# AEMSUCA-R2.net
KiCad netlist of a schematic drawn in EAGLE
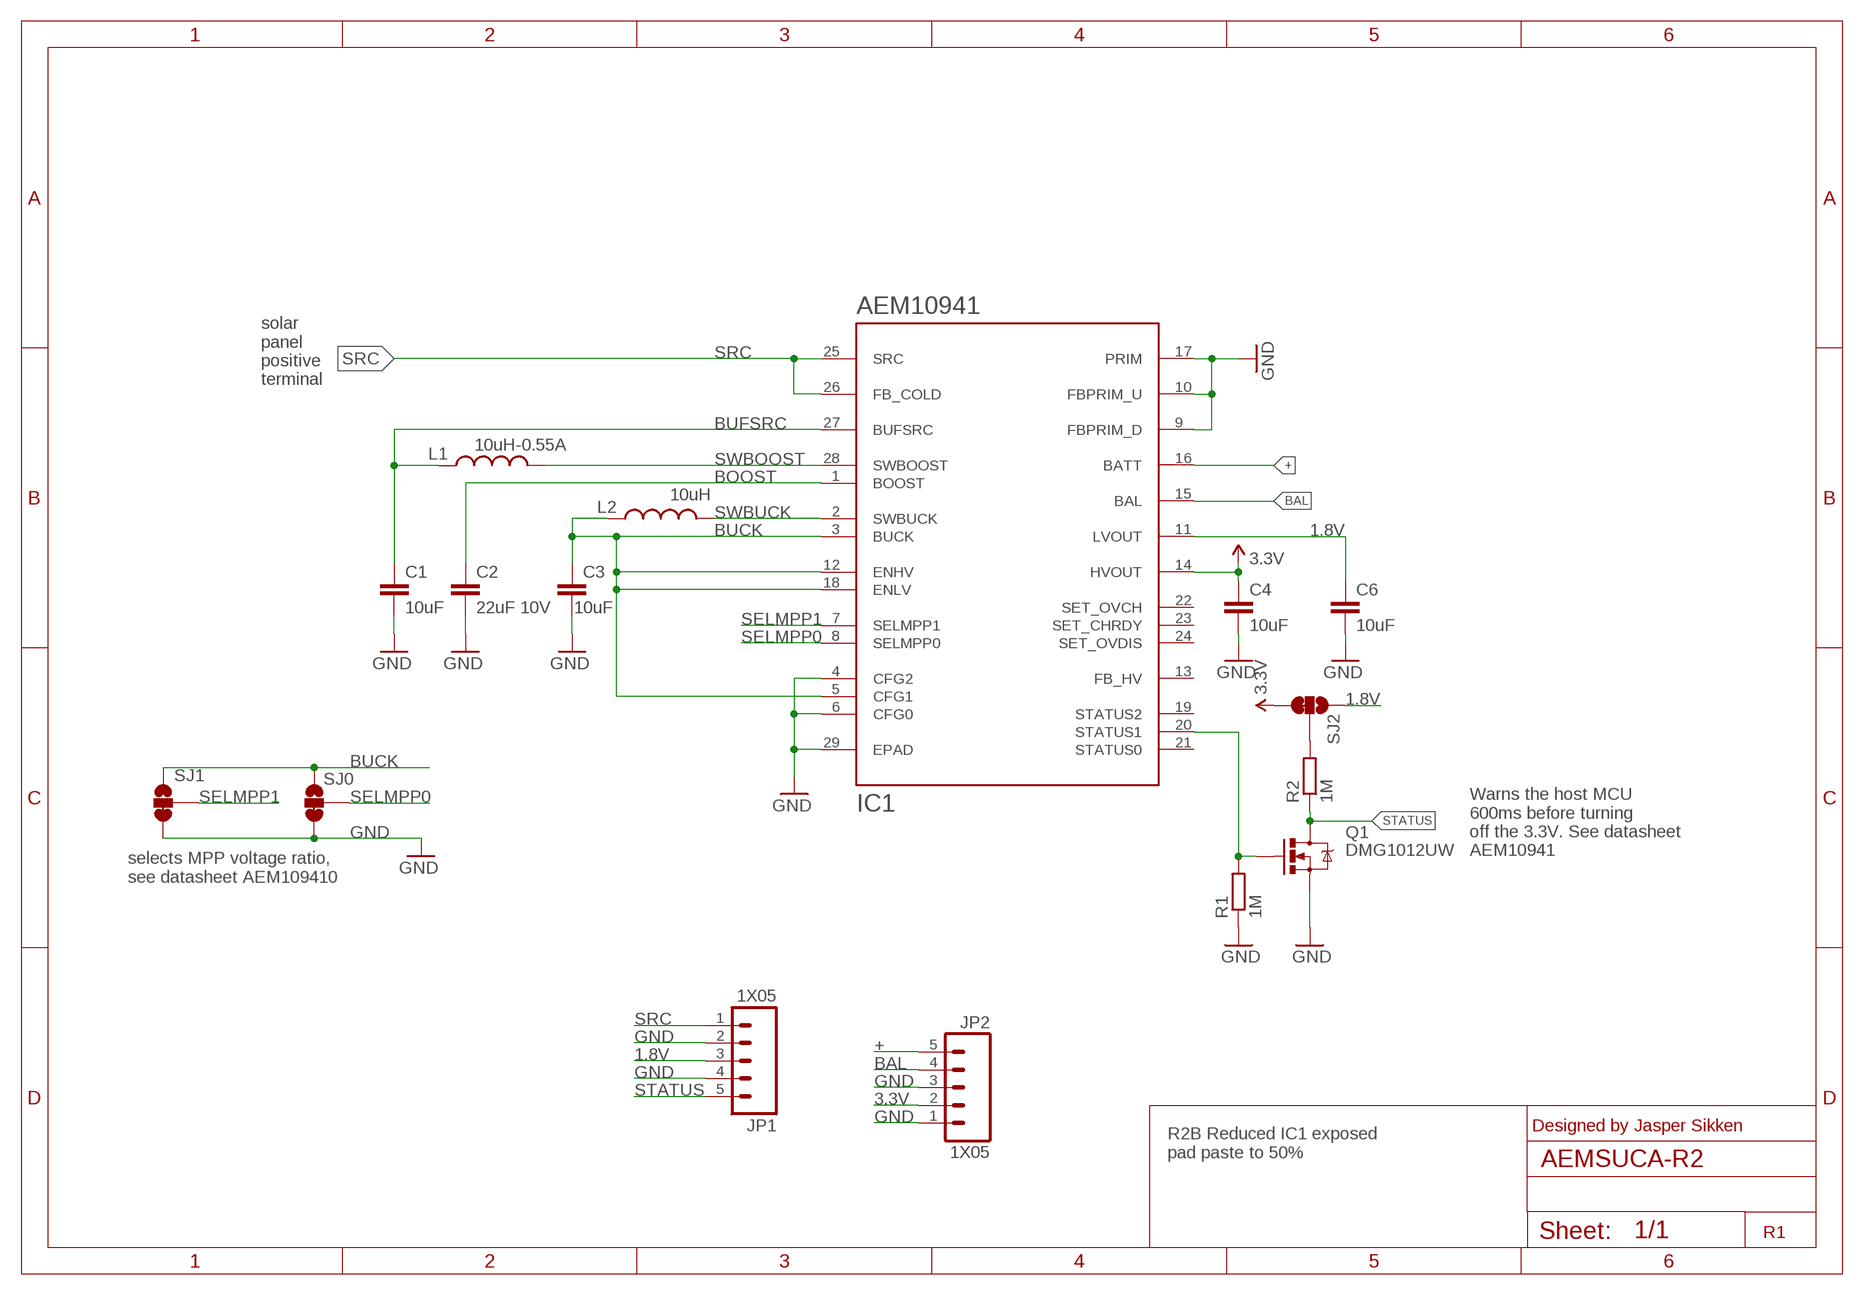
[diagram p0: schematic, sheet 1]

(export (version "E")
  (design (tool "Eeschema 10.0.6"))
  (components
    (comp (ref "C1")
      (value "10uF")
      (footprint "eagle-import:C0603")
      (fields (field (name "MF") "Taiyo Yuden") (field (name "MPN") "LMK107BBJ106MALT"))
      (libsource (lib "eagle-import") (part "C0603_10UF"))
    )
    (comp (ref "C2")
      (value "22uF 10V")
      (footprint "eagle-import:C0603")
      (fields (field (name "MF") "Murata") (field (name "MPN") "GRM188R61A226ME15D"))
      (libsource (lib "eagle-import") (part "C0603_22UF"))
    )
    (comp (ref "C3")
      (value "10uF")
      (footprint "eagle-import:C0603")
      (fields (field (name "MF") "Taiyo Yuden") (field (name "MPN") "LMK107BBJ106MALT"))
      (libsource (lib "eagle-import") (part "C0603_10UF"))
    )
    (comp (ref "C4")
      (value "10uF")
      (footprint "eagle-import:C0603")
      (fields (field (name "MF") "Taiyo Yuden") (field (name "MPN") "LMK107BBJ106MALT"))
      (libsource (lib "eagle-import") (part "C0603_10UF"))
    )
    (comp (ref "C6")
      (value "10uF")
      (footprint "eagle-import:C0603")
      (fields (field (name "MF") "Taiyo Yuden") (field (name "MPN") "LMK107BBJ106MALT"))
      (libsource (lib "eagle-import") (part "C0603_10UF"))
    )
    (comp (ref "IC1")
      (value "AEM10941")
      (footprint "eagle-import:QFN50P505X505X90-28")
      (fields (field (name "MF") "e-peas"))
      (libsource (lib "eagle-import") (part "AEM10941"))
    )
    (comp (ref "JP1")
      (value "1X05")
      (footprint "eagle-import:1X05_2.54MM_ROUND_NOSILK")
      (libsource (lib "eagle-import") (part "1X05"))
    )
    (comp (ref "JP2")
      (value "1X05")
      (footprint "eagle-import:1X05_2.54MM_ROUND_NOSILK")
      (libsource (lib "eagle-import") (part "1X05"))
    )
    (comp (ref "L1")
      (value "10uH-0.55A")
      (footprint "eagle-import:LPS4012")
      (fields (field (name "MF") "Coilcraft") (field (name "MPN") "LPS4012-103MRB"))
      (libsource (lib "eagle-import") (part "L3.9X3.9_10UH_0.55A"))
    )
    (comp (ref "L2")
      (value "10uH")
      (footprint "eagle-import:L0603")
      (fields (field (name "MF") "TDK") (field (name "MPN") "MLZ1608M100WT"))
      (libsource (lib "eagle-import") (part "L0603_10UH"))
    )
    (comp (ref "Q1")
      (value "DMG1012UW")
      (footprint "eagle-import:SOT323")
      (fields (field (name "MF") "Diodes") (field (name "MPN") "DMG1012UW-7"))
      (libsource (lib "eagle-import") (part "MOSFET-N-CHANNEL_DMG1012UW"))
    )
    (comp (ref "R1")
      (value "1M")
      (footprint "eagle-import:R0402")
      (fields (field (name "MF") "Walsin") (field (name "MPN") "WR04X1004FTL"))
      (libsource (lib "eagle-import") (part "R0402_1M"))
    )
    (comp (ref "R2")
      (value "1M")
      (footprint "eagle-import:R0402")
      (fields (field (name "MF") "Walsin") (field (name "MPN") "WR04X1004FTL"))
      (libsource (lib "eagle-import") (part "R0402_1M"))
    )
    (comp (ref "SJ0")
      (value "SOLDERJUMPER_3WAY_12SHORT3WAY")
      (footprint "eagle-import:SJ_3S_NC_0402")
      (libsource (lib "eagle-import") (part "SOLDERJUMPER_3WAY_12SHORT3WAY"))
    )
    (comp (ref "SJ1")
      (value "SOLDERJUMPER_3WAY_12SHORT3WAY")
      (footprint "eagle-import:SJ_3S_NC_0402")
      (libsource (lib "eagle-import") (part "SOLDERJUMPER_3WAY_12SHORT3WAY"))
    )
    (comp (ref "SJ2")
      (value "SOLDERJUMPER_3WAY_12SHORT3WAY")
      (footprint "eagle-import:SJ_3S_NC_0402")
      (libsource (lib "eagle-import") (part "SOLDERJUMPER_3WAY_12SHORT3WAY"))
    )
  )
  (nets
    (net (code "1") (name "+") (class "Default")
      (node (ref "IC1") (pin "16") (pinfunction "BATT_16") (pintype "bidirectional"))
      (node (ref "JP2") (pin "5") (pinfunction "5_5") (pintype "passive"))
    )
    (net (code "2") (name "/1.8V") (class "Default")
      (node (ref "C6") (pin "1") (pinfunction "1_1") (pintype "passive"))
      (node (ref "IC1") (pin "11") (pinfunction "LVOUT_11") (pintype "bidirectional"))
      (node (ref "JP1") (pin "3") (pinfunction "3_3") (pintype "passive"))
      (node (ref "SJ2") (pin "3") (pinfunction "3_3") (pintype "passive"))
    )
    (net (code "3") (name "/BOOST") (class "Default")
      (node (ref "C2") (pin "1") (pinfunction "1_1") (pintype "passive"))
      (node (ref "IC1") (pin "1") (pinfunction "BOOST_1") (pintype "bidirectional"))
    )
    (net (code "4") (name "/BUCK") (class "Default")
      (node (ref "C3") (pin "1") (pinfunction "1_1") (pintype "passive"))
      (node (ref "IC1") (pin "12") (pinfunction "ENHV_12") (pintype "bidirectional"))
      (node (ref "IC1") (pin "18") (pinfunction "ENLV_18") (pintype "bidirectional"))
      (node (ref "IC1") (pin "3") (pinfunction "BUCK_3") (pintype "bidirectional"))
      (node (ref "IC1") (pin "5") (pinfunction "CFG1_5") (pintype "bidirectional"))
      (node (ref "L2") (pin "1") (pinfunction "1_1") (pintype "passive"))
      (node (ref "SJ0") (pin "3") (pinfunction "3_3") (pintype "passive"))
      (node (ref "SJ1") (pin "3") (pinfunction "3_3") (pintype "passive"))
    )
    (net (code "5") (name "/BUFSRC") (class "Default")
      (node (ref "C1") (pin "1") (pinfunction "1_1") (pintype "passive"))
      (node (ref "IC1") (pin "27") (pinfunction "BUFSRC_27") (pintype "power_in"))
      (node (ref "L1") (pin "1") (pinfunction "1_1") (pintype "passive"))
    )
    (net (code "6") (name "/SELMPP0") (class "Default")
      (node (ref "IC1") (pin "8") (pinfunction "SELMPP0_8") (pintype "bidirectional"))
      (node (ref "SJ0") (pin "2") (pinfunction "2_2") (pintype "passive"))
    )
    (net (code "7") (name "/SELMPP1") (class "Default")
      (node (ref "IC1") (pin "7") (pinfunction "SELMPP1_7") (pintype "bidirectional"))
      (node (ref "SJ1") (pin "2") (pinfunction "2_2") (pintype "passive"))
    )
    (net (code "8") (name "/SWBOOST") (class "Default")
      (node (ref "IC1") (pin "28") (pinfunction "SWBOOST_28") (pintype "power_in"))
      (node (ref "L1") (pin "2") (pinfunction "2_2") (pintype "passive"))
    )
    (net (code "9") (name "/SWBUCK") (class "Default")
      (node (ref "IC1") (pin "2") (pinfunction "SWBUCK_2") (pintype "bidirectional"))
      (node (ref "L2") (pin "2") (pinfunction "2_2") (pintype "passive"))
    )
    (net (code "10") (name "3.3V") (class "Default")
      (node (ref "C4") (pin "1") (pinfunction "1_1") (pintype "passive"))
      (node (ref "IC1") (pin "14") (pinfunction "HVOUT_14") (pintype "bidirectional"))
      (node (ref "JP2") (pin "2") (pinfunction "2_2") (pintype "passive"))
      (node (ref "SJ2") (pin "1") (pinfunction "1_1") (pintype "passive"))
    )
    (net (code "11") (name "BAL") (class "Default")
      (node (ref "IC1") (pin "15") (pinfunction "BAL_15") (pintype "bidirectional"))
      (node (ref "JP2") (pin "4") (pinfunction "4_4") (pintype "passive"))
    )
    (net (code "12") (name "GND") (class "Default")
      (node (ref "C1") (pin "2") (pinfunction "2_2") (pintype "passive"))
      (node (ref "C2") (pin "2") (pinfunction "2_2") (pintype "passive"))
      (node (ref "C3") (pin "2") (pinfunction "2_2") (pintype "passive"))
      (node (ref "C4") (pin "2") (pinfunction "2_2") (pintype "passive"))
      (node (ref "C6") (pin "2") (pinfunction "2_2") (pintype "passive"))
      (node (ref "IC1") (pin "10") (pinfunction "FBPRIM_U_10") (pintype "bidirectional"))
      (node (ref "IC1") (pin "17") (pinfunction "PRIM_17") (pintype "bidirectional"))
      (node (ref "IC1") (pin "29") (pinfunction "EPAD_29") (pintype "power_in"))
      (node (ref "IC1") (pin "4") (pinfunction "CFG2_4") (pintype "bidirectional"))
      (node (ref "IC1") (pin "6") (pinfunction "CFG0_6") (pintype "bidirectional"))
      (node (ref "IC1") (pin "9") (pinfunction "FBPRIM_D_9") (pintype "bidirectional"))
      (node (ref "JP1") (pin "2") (pinfunction "2_2") (pintype "passive"))
      (node (ref "JP1") (pin "4") (pinfunction "4_4") (pintype "passive"))
      (node (ref "JP2") (pin "1") (pinfunction "1_1") (pintype "passive"))
      (node (ref "JP2") (pin "3") (pinfunction "3_3") (pintype "passive"))
      (node (ref "Q1") (pin "2") (pinfunction "S_2") (pintype "passive"))
      (node (ref "R1") (pin "1") (pinfunction "1_1") (pintype "passive"))
      (node (ref "SJ0") (pin "1") (pinfunction "1_1") (pintype "passive"))
      (node (ref "SJ1") (pin "1") (pinfunction "1_1") (pintype "passive"))
    )
    (net (code "13") (name "Net-(IC1-STATUS1)") (class "Default")
      (node (ref "IC1") (pin "20") (pinfunction "STATUS1_20") (pintype "bidirectional"))
      (node (ref "Q1") (pin "1") (pinfunction "G_1") (pintype "passive"))
      (node (ref "R1") (pin "2") (pinfunction "2_2") (pintype "passive"))
    )
    (net (code "14") (name "Net-(R2-Pad2)") (class "Default")
      (node (ref "R2") (pin "2") (pinfunction "2_2") (pintype "passive"))
      (node (ref "SJ2") (pin "2") (pinfunction "2_2") (pintype "passive"))
    )
    (net (code "15") (name "SRC") (class "Default")
      (node (ref "IC1") (pin "25") (pinfunction "SRC_25") (pintype "power_in"))
      (node (ref "IC1") (pin "26") (pinfunction "FB_COLD_26") (pintype "input"))
      (node (ref "JP1") (pin "1") (pinfunction "1_1") (pintype "passive"))
    )
    (net (code "16") (name "STATUS") (class "Default")
      (node (ref "JP1") (pin "5") (pinfunction "5_5") (pintype "passive"))
      (node (ref "Q1") (pin "3") (pinfunction "D_3") (pintype "passive"))
      (node (ref "R2") (pin "1") (pinfunction "1_1") (pintype "passive"))
    )
    (net (code "17") (name "unconnected-(IC1-FB_HV-Pad13)") (class "Default")
      (node (ref "IC1") (pin "13") (pinfunction "FB_HV_13") (pintype "bidirectional"))
    )
    (net (code "18") (name "unconnected-(IC1-SET_CHRDY-Pad23)") (class "Default")
      (node (ref "IC1") (pin "23") (pinfunction "SET_CHRDY_23") (pintype "bidirectional"))
    )
    (net (code "19") (name "unconnected-(IC1-SET_OVCH-Pad22)") (class "Default")
      (node (ref "IC1") (pin "22") (pinfunction "SET_OVCH_22") (pintype "bidirectional"))
    )
    (net (code "20") (name "unconnected-(IC1-SET_OVDIS-Pad24)") (class "Default")
      (node (ref "IC1") (pin "24") (pinfunction "SET_OVDIS_24") (pintype "bidirectional"))
    )
    (net (code "21") (name "unconnected-(IC1-STATUS0-Pad21)") (class "Default")
      (node (ref "IC1") (pin "21") (pinfunction "STATUS0_21") (pintype "bidirectional"))
    )
    (net (code "22") (name "unconnected-(IC1-STATUS2-Pad19)") (class "Default")
      (node (ref "IC1") (pin "19") (pinfunction "STATUS2_19") (pintype "bidirectional"))
    )
  )
)
